# HW2_Brian_Burton_u1038667.net
KiCad netlist of a schematic drawn in EAGLE
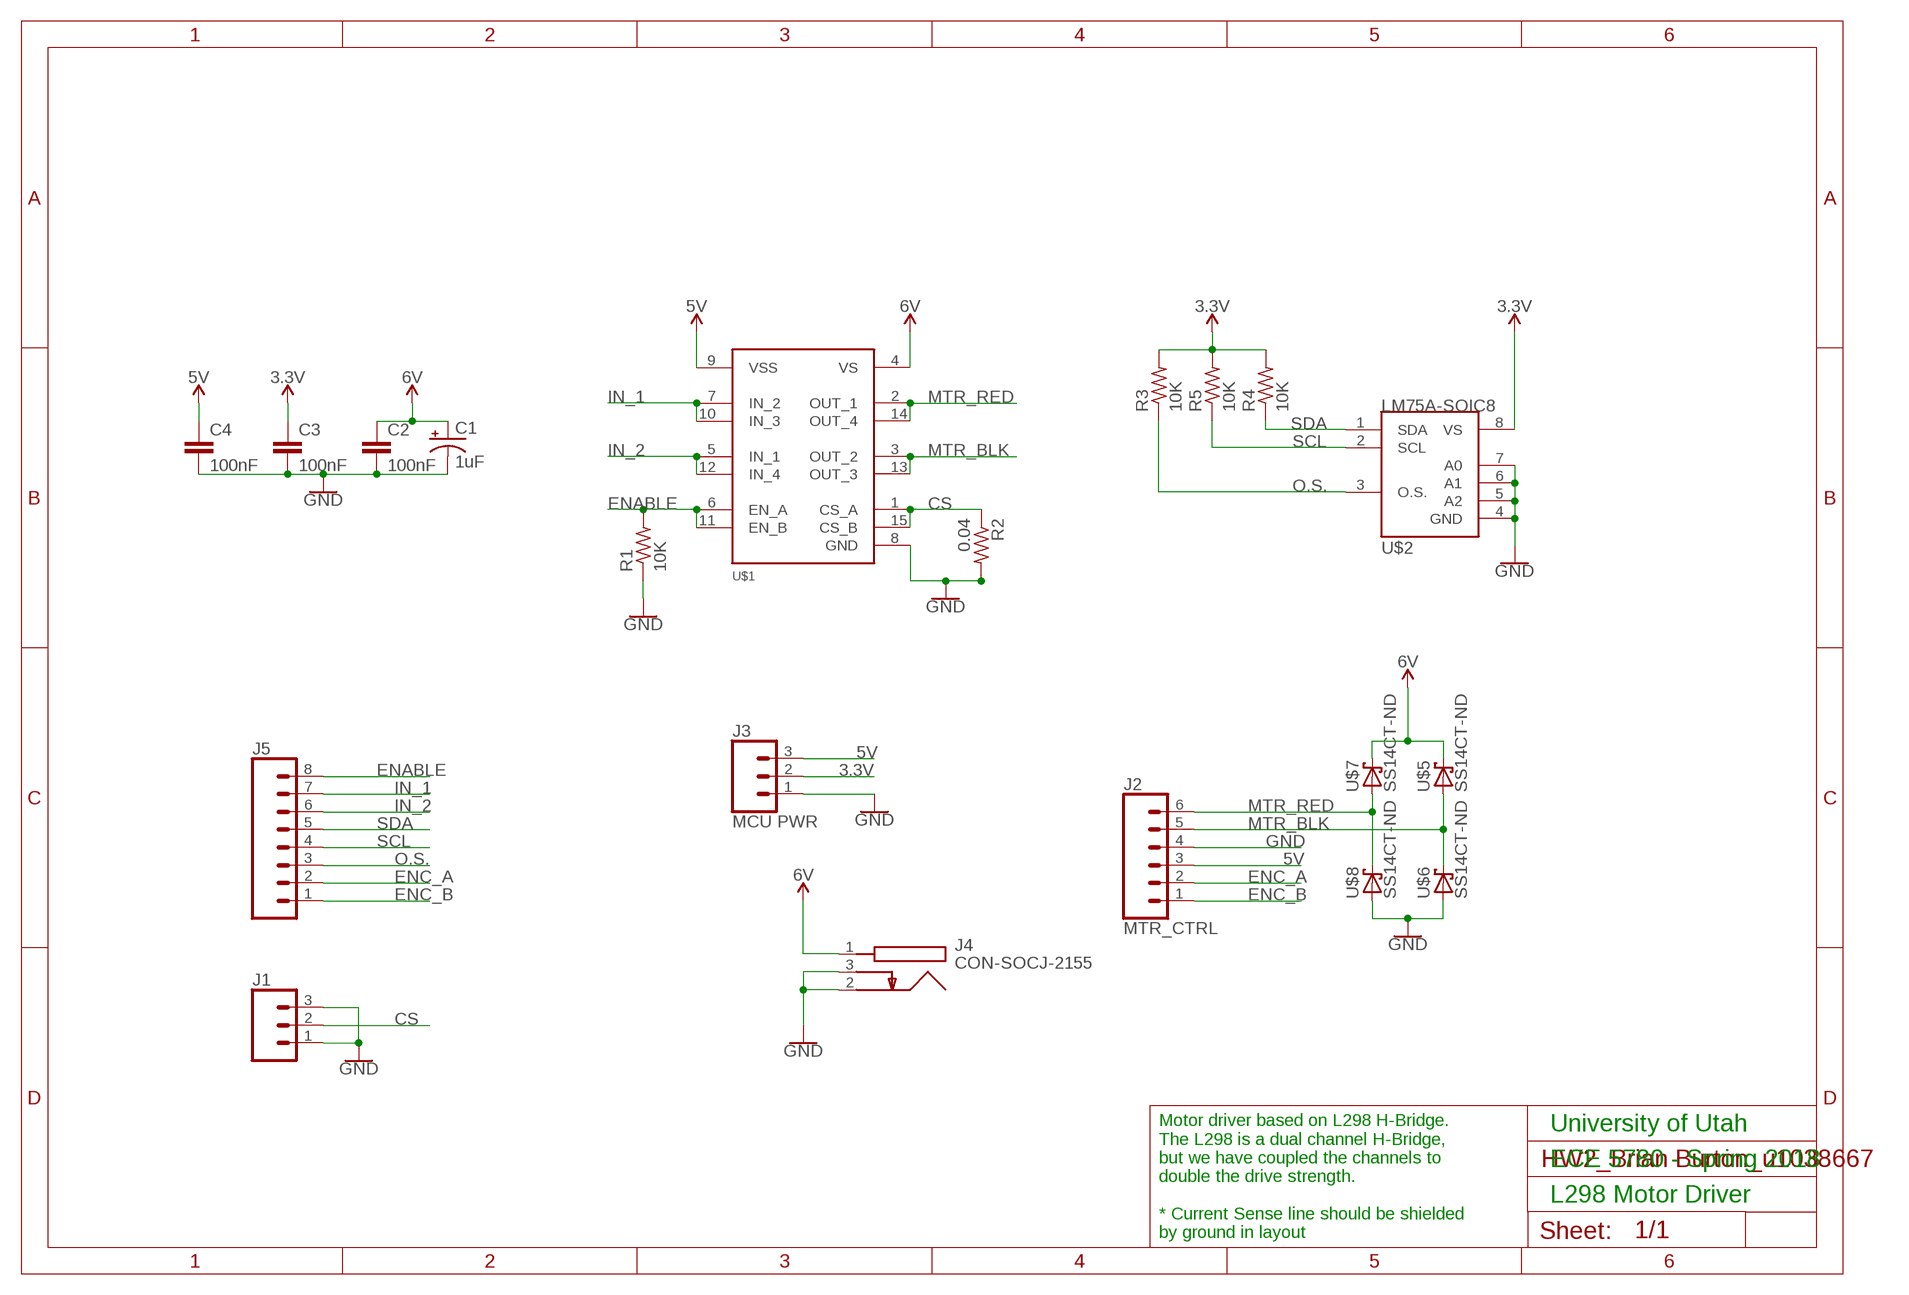
[diagram p0: schematic, sheet 1]

(export (version "E")
  (design (tool "Eeschema 10.0.6"))
  (components
    (comp (ref "C1")
      (value "1uF")
      (footprint "eagle-import:E2,5-6")
      (libsource (lib "eagle-import") (part "CPOL-USE2.5-6"))
    )
    (comp (ref "C2")
      (value "100nF")
      (footprint "eagle-import:C1206")
      (libsource (lib "eagle-import") (part "C-EUC1206"))
    )
    (comp (ref "C3")
      (value "100nF")
      (footprint "eagle-import:C1206")
      (libsource (lib "eagle-import") (part "C-EUC1206"))
    )
    (comp (ref "C4")
      (value "100nF")
      (footprint "eagle-import:C1206")
      (libsource (lib "eagle-import") (part "C-EUC1206"))
    )
    (comp (ref "J1")
      (value "CONN_03")
      (footprint "eagle-import:1X03")
      (libsource (lib "eagle-import") (part "CONN_03"))
    )
    (comp (ref "J2")
      (value "MTR_CTRL")
      (footprint "eagle-import:1X06")
      (libsource (lib "eagle-import") (part "CONN_06SILK_FEMALE_PTH"))
    )
    (comp (ref "J3")
      (value "MCU PWR")
      (footprint "eagle-import:1X03")
      (libsource (lib "eagle-import") (part "CONN_03"))
    )
    (comp (ref "J4")
      (value "CON-SOCJ-2155")
      (footprint "eagle-import:CONSOCJ2155")
      (fields (field (name "MOUSER_PART_NUMBER") "992-CON-SOCJ-2155"))
      (libsource (lib "eagle-import") (part "CON-SOCJ-2155"))
    )
    (comp (ref "J5")
      (value "CONN_08\"")
      (footprint "eagle-import:1X08")
      (libsource (lib "eagle-import") (part "CONN_08{dblquote}"))
    )
    (comp (ref "R1")
      (value "10K")
      (footprint "eagle-import:M1206")
      (libsource (lib "eagle-import") (part "R-US_M1206"))
    )
    (comp (ref "R2")
      (value "0.04")
      (footprint "eagle-import:M1206")
      (libsource (lib "eagle-import") (part "R-US_M1206"))
    )
    (comp (ref "R3")
      (value "10K")
      (footprint "eagle-import:M1206")
      (libsource (lib "eagle-import") (part "R-US_M1206"))
    )
    (comp (ref "R4")
      (value "10K")
      (footprint "eagle-import:M1206")
      (libsource (lib "eagle-import") (part "R-US_M1206"))
    )
    (comp (ref "R5")
      (value "10K")
      (footprint "eagle-import:M1206")
      (libsource (lib "eagle-import") (part "R-US_M1206"))
    )
    (comp (ref "U$1")
      (value "L298N-MULTIWATT15")
      (footprint "eagle-import:L298N-MULTIWATT15")
      (libsource (lib "eagle-import") (part "L298N-MULTIWATT15"))
    )
    (comp (ref "U$2")
      (value "LM75A-SOIC8")
      (footprint "eagle-import:SOIC-8")
      (libsource (lib "eagle-import") (part "LM75A-SOIC8"))
    )
    (comp (ref "U$5")
      (value "SS14CT-ND")
      (footprint "eagle-import:SOD106A-W")
      (libsource (lib "eagle-import") (part "SS14CT-ND"))
    )
    (comp (ref "U$6")
      (value "SS14CT-ND")
      (footprint "eagle-import:SOD106A-W")
      (libsource (lib "eagle-import") (part "SS14CT-ND"))
    )
    (comp (ref "U$7")
      (value "SS14CT-ND")
      (footprint "eagle-import:SOD106A-W")
      (libsource (lib "eagle-import") (part "SS14CT-ND"))
    )
    (comp (ref "U$8")
      (value "SS14CT-ND")
      (footprint "eagle-import:SOD106A-W")
      (libsource (lib "eagle-import") (part "SS14CT-ND"))
    )
  )
  (nets
    (net (code "1") (name "/CS") (class "Default")
      (node (ref "J1") (pin "2") (pinfunction "2_2") (pintype "passive"))
      (node (ref "R2") (pin "1") (pinfunction "1_1") (pintype "passive"))
      (node (ref "U$1") (pin "1") (pinfunction "CS_A_1") (pintype "bidirectional"))
      (node (ref "U$1") (pin "15") (pinfunction "CS_B_15") (pintype "bidirectional"))
    )
    (net (code "2") (name "/ENABLE") (class "Default")
      (node (ref "J5") (pin "8") (pinfunction "8_8") (pintype "passive"))
      (node (ref "R1") (pin "2") (pinfunction "2_2") (pintype "passive"))
      (node (ref "U$1") (pin "11") (pinfunction "EN_B_11") (pintype "bidirectional"))
      (node (ref "U$1") (pin "6") (pinfunction "EN_A_6") (pintype "bidirectional"))
    )
    (net (code "3") (name "/ENC_A") (class "Default")
      (node (ref "J2") (pin "2") (pinfunction "2_2") (pintype "passive"))
      (node (ref "J5") (pin "2") (pinfunction "2_2") (pintype "passive"))
    )
    (net (code "4") (name "/ENC_B") (class "Default")
      (node (ref "J2") (pin "1") (pinfunction "1_1") (pintype "passive"))
      (node (ref "J5") (pin "1") (pinfunction "1_1") (pintype "passive"))
    )
    (net (code "5") (name "/IN_1") (class "Default")
      (node (ref "J5") (pin "7") (pinfunction "7_7") (pintype "passive"))
      (node (ref "U$1") (pin "10") (pinfunction "IN_3_10") (pintype "bidirectional"))
      (node (ref "U$1") (pin "7") (pinfunction "IN_2_7") (pintype "bidirectional"))
    )
    (net (code "6") (name "/IN_2") (class "Default")
      (node (ref "J5") (pin "6") (pinfunction "6_6") (pintype "passive"))
      (node (ref "U$1") (pin "12") (pinfunction "IN_4_12") (pintype "bidirectional"))
      (node (ref "U$1") (pin "5") (pinfunction "IN_1_5") (pintype "bidirectional"))
    )
    (net (code "7") (name "/MTR_BLK") (class "Default")
      (node (ref "J2") (pin "5") (pinfunction "5_5") (pintype "passive"))
      (node (ref "U$1") (pin "13") (pinfunction "OUT_3_13") (pintype "bidirectional"))
      (node (ref "U$1") (pin "3") (pinfunction "OUT_2_3") (pintype "bidirectional"))
      (node (ref "U$5") (pin "A") (pinfunction "A_A") (pintype "passive"))
      (node (ref "U$6") (pin "C") (pinfunction "C_C") (pintype "passive"))
    )
    (net (code "8") (name "/MTR_RED") (class "Default")
      (node (ref "J2") (pin "6") (pinfunction "6_6") (pintype "passive"))
      (node (ref "U$1") (pin "14") (pinfunction "OUT_4_14") (pintype "bidirectional"))
      (node (ref "U$1") (pin "2") (pinfunction "OUT_1_2") (pintype "bidirectional"))
      (node (ref "U$7") (pin "A") (pinfunction "A_A") (pintype "passive"))
      (node (ref "U$8") (pin "C") (pinfunction "C_C") (pintype "passive"))
    )
    (net (code "9") (name "/O.S.") (class "Default")
      (node (ref "J5") (pin "3") (pinfunction "3_3") (pintype "passive"))
      (node (ref "R3") (pin "1") (pinfunction "1_1") (pintype "passive"))
      (node (ref "U$2") (pin "3") (pinfunction "O.S._3") (pintype "bidirectional"))
    )
    (net (code "10") (name "/SCL") (class "Default")
      (node (ref "J5") (pin "4") (pinfunction "4_4") (pintype "passive"))
      (node (ref "R5") (pin "1") (pinfunction "1_1") (pintype "passive"))
      (node (ref "U$2") (pin "2") (pinfunction "SCL_2") (pintype "bidirectional"))
    )
    (net (code "11") (name "/SDA") (class "Default")
      (node (ref "J5") (pin "5") (pinfunction "5_5") (pintype "passive"))
      (node (ref "R4") (pin "1") (pinfunction "1_1") (pintype "passive"))
      (node (ref "U$2") (pin "1") (pinfunction "SDA_1") (pintype "bidirectional"))
    )
    (net (code "12") (name "3.3V") (class "Default")
      (node (ref "C3") (pin "1") (pinfunction "1_1") (pintype "passive"))
      (node (ref "J3") (pin "2") (pinfunction "2_2") (pintype "passive"))
      (node (ref "R3") (pin "2") (pinfunction "2_2") (pintype "passive"))
      (node (ref "R4") (pin "2") (pinfunction "2_2") (pintype "passive"))
      (node (ref "R5") (pin "2") (pinfunction "2_2") (pintype "passive"))
      (node (ref "U$2") (pin "8") (pinfunction "VS_8") (pintype "bidirectional"))
    )
    (net (code "13") (name "5V") (class "Default")
      (node (ref "C4") (pin "1") (pinfunction "1_1") (pintype "passive"))
      (node (ref "J2") (pin "3") (pinfunction "3_3") (pintype "passive"))
      (node (ref "J3") (pin "3") (pinfunction "3_3") (pintype "passive"))
      (node (ref "U$1") (pin "9") (pinfunction "VSS_9") (pintype "bidirectional"))
    )
    (net (code "14") (name "6V") (class "Default")
      (node (ref "C1") (pin "+") (pinfunction "+_+") (pintype "passive"))
      (node (ref "C2") (pin "1") (pinfunction "1_1") (pintype "passive"))
      (node (ref "J4") (pin "1") (pinfunction "1_1") (pintype "bidirectional"))
      (node (ref "U$1") (pin "4") (pinfunction "VS_4") (pintype "bidirectional"))
      (node (ref "U$5") (pin "C") (pinfunction "C_C") (pintype "passive"))
      (node (ref "U$7") (pin "C") (pinfunction "C_C") (pintype "passive"))
    )
    (net (code "15") (name "GND") (class "Default")
      (node (ref "C1") (pin "-") (pinfunction "-_-") (pintype "passive"))
      (node (ref "C2") (pin "2") (pinfunction "2_2") (pintype "passive"))
      (node (ref "C3") (pin "2") (pinfunction "2_2") (pintype "passive"))
      (node (ref "C4") (pin "2") (pinfunction "2_2") (pintype "passive"))
      (node (ref "J1") (pin "1") (pinfunction "1_1") (pintype "passive"))
      (node (ref "J1") (pin "3") (pinfunction "3_3") (pintype "passive"))
      (node (ref "J2") (pin "4") (pinfunction "4_4") (pintype "passive"))
      (node (ref "J3") (pin "1") (pinfunction "1_1") (pintype "passive"))
      (node (ref "J4") (pin "2") (pinfunction "2_2") (pintype "bidirectional"))
      (node (ref "J4") (pin "3") (pinfunction "3_3") (pintype "bidirectional"))
      (node (ref "R1") (pin "1") (pinfunction "1_1") (pintype "passive"))
      (node (ref "R2") (pin "2") (pinfunction "2_2") (pintype "passive"))
      (node (ref "U$1") (pin "8") (pinfunction "GND_8") (pintype "bidirectional"))
      (node (ref "U$2") (pin "4") (pinfunction "GND_4") (pintype "bidirectional"))
      (node (ref "U$2") (pin "5") (pinfunction "A2_5") (pintype "bidirectional"))
      (node (ref "U$2") (pin "6") (pinfunction "A1_6") (pintype "bidirectional"))
      (node (ref "U$2") (pin "7") (pinfunction "A0_7") (pintype "bidirectional"))
      (node (ref "U$6") (pin "A") (pinfunction "A_A") (pintype "passive"))
      (node (ref "U$8") (pin "A") (pinfunction "A_A") (pintype "passive"))
    )
  )
)
